# rev10.net
KiCad netlist of a schematic drawn in EAGLE
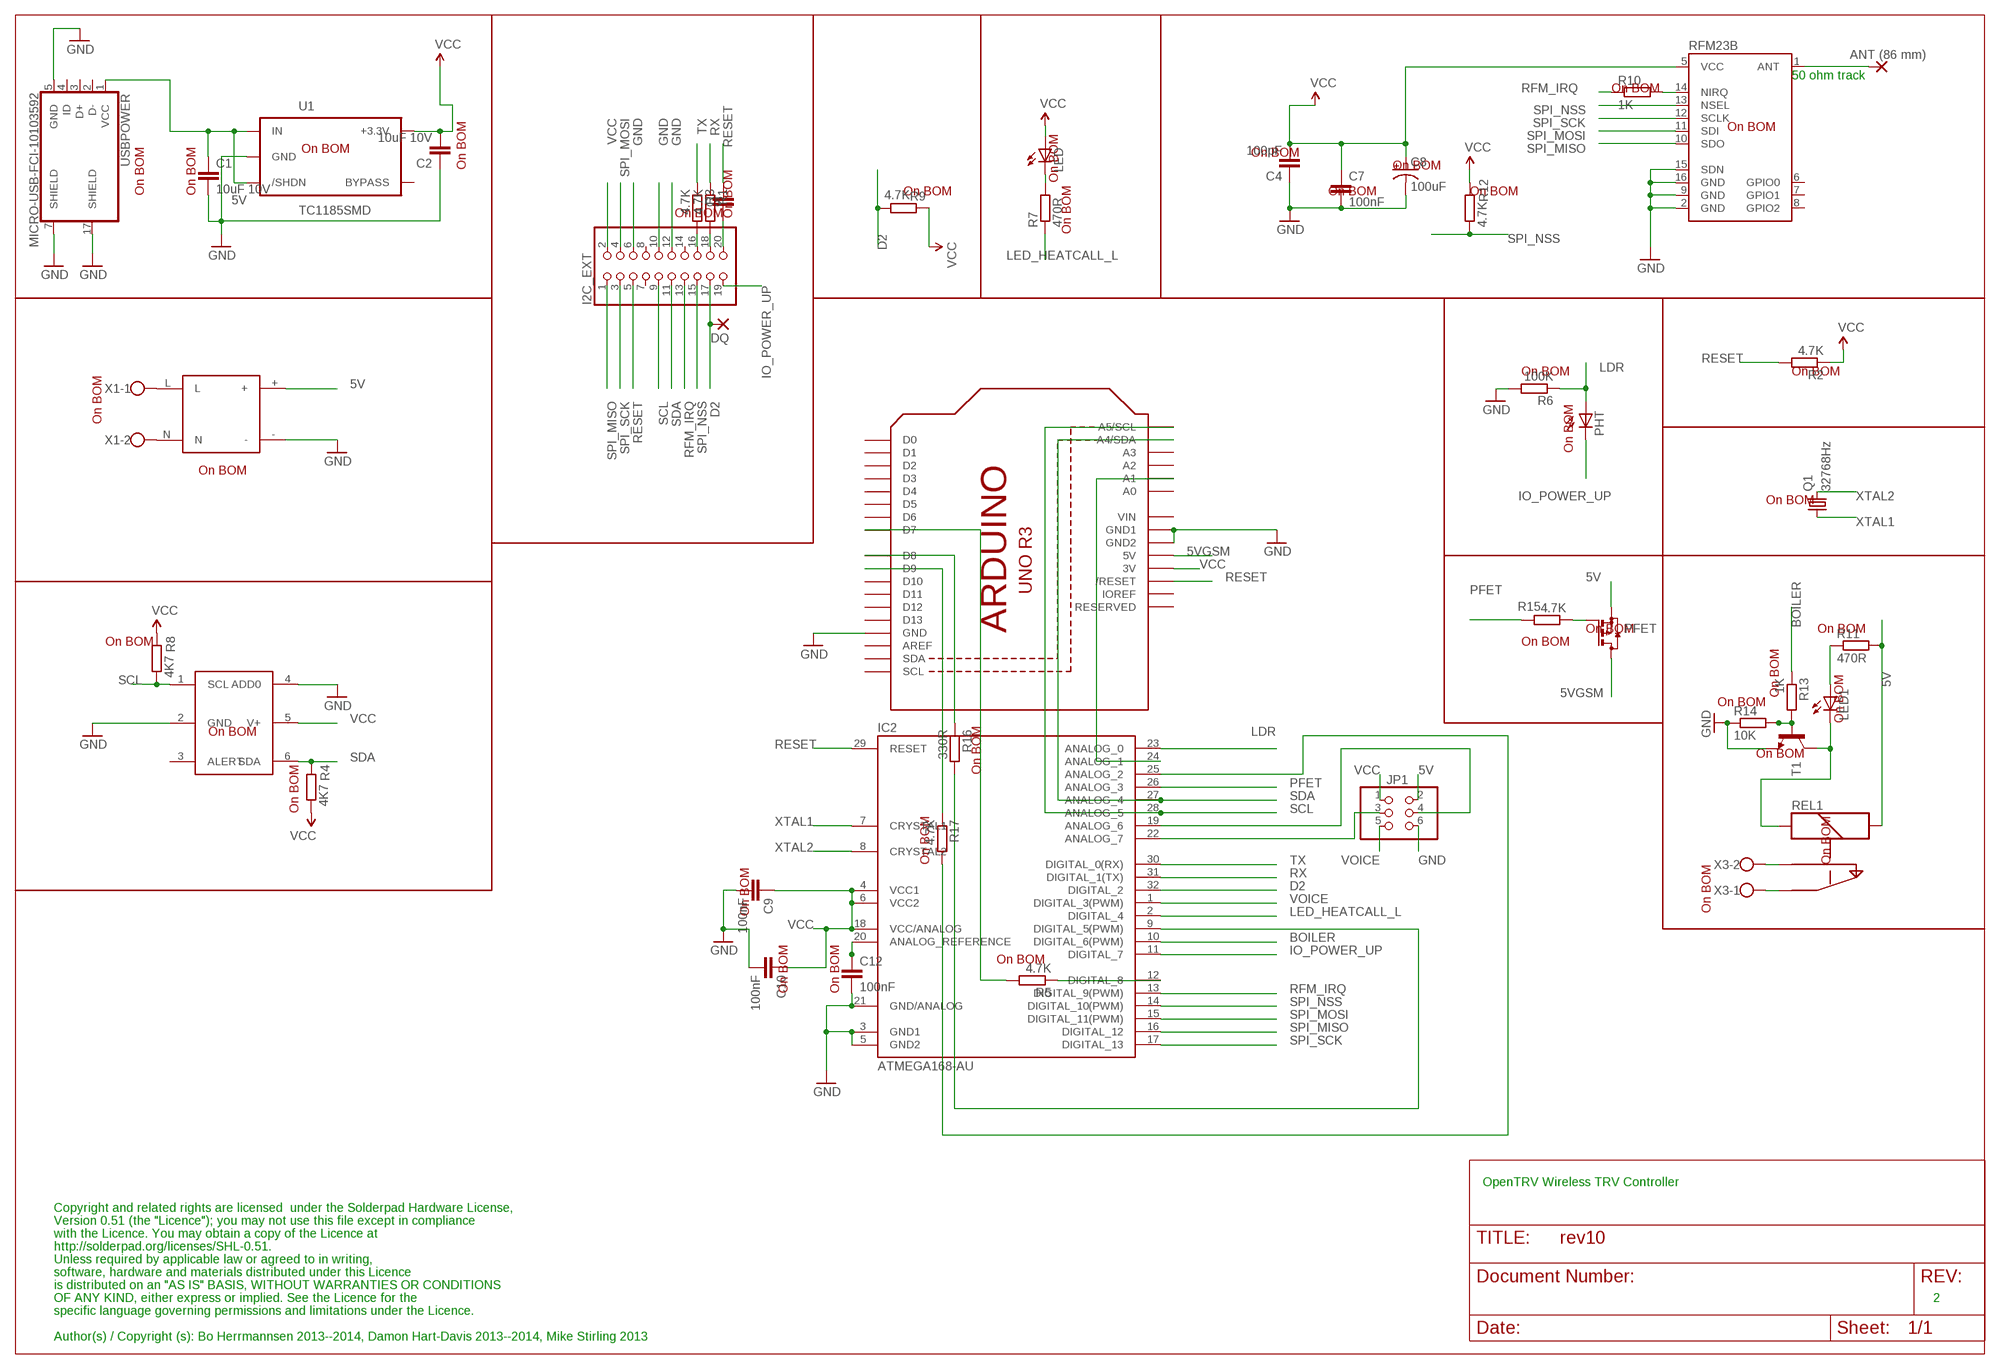
[diagram p0: schematic, sheet 1]

(export (version "E")
  (design (tool "Eeschema 10.0.6"))
  (components
    (comp (ref "ANT1")
      (value "ANT (86 mm)")
      (footprint "eagle-import:2,15_1,0")
      (libsource (lib "eagle-import") (part "2,15/1,0"))
    )
    (comp (ref "C1")
      (value "10uF 10V")
      (footprint "eagle-import:C0603")
      (libsource (lib "eagle-import") (part "C-EUC0603"))
    )
    (comp (ref "C2")
      (value "10uF 10V")
      (footprint "eagle-import:C0603")
      (libsource (lib "eagle-import") (part "C-EUC0603"))
    )
    (comp (ref "C4")
      (value "100pF")
      (footprint "eagle-import:C0603")
      (libsource (lib "eagle-import") (part "C-EUC0603"))
    )
    (comp (ref "C5")
      (value "100nF")
      (footprint "eagle-import:C0603")
      (libsource (lib "eagle-import") (part "C-EUC0603"))
    )
    (comp (ref "C7")
      (value "100nF")
      (footprint "eagle-import:C0603")
      (libsource (lib "eagle-import") (part "C-EUC0603"))
    )
    (comp (ref "C8")
      (value "100uF")
      (footprint "eagle-import:EIA3216")
      (libsource (lib "eagle-import") (part "CAP_POL1206"))
    )
    (comp (ref "C9")
      (value "100nF")
      (footprint "eagle-import:C0603")
      (libsource (lib "eagle-import") (part "C-EUC0603"))
    )
    (comp (ref "C10")
      (value "100nF")
      (footprint "eagle-import:C0603")
      (libsource (lib "eagle-import") (part "C-EUC0603"))
    )
    (comp (ref "C12")
      (value "100nF")
      (footprint "eagle-import:C0603")
      (libsource (lib "eagle-import") (part "C-EUC0603"))
    )
    (comp (ref "DQ")
      (value "2,15/1,0")
      (footprint "eagle-import:2,15_1,0")
      (libsource (lib "eagle-import") (part "2,15/1,0"))
    )
    (comp (ref "I2C_EXT")
      (value "PINHD-2X10")
      (footprint "eagle-import:2X10")
      (libsource (lib "eagle-import") (part "PINHD-2X10"))
    )
    (comp (ref "IC2")
      (value "ATMEGA168-AU")
      (footprint "eagle-import:TQFP32-08")
      (libsource (lib "eagle-import") (part "ATMEGA168-AU"))
    )
    (comp (ref "JP1")
      (value "PINHD-2X3")
      (footprint "eagle-import:2X03")
      (libsource (lib "eagle-import") (part "PINHD-2X3"))
    )
    (comp (ref "LED")
      (value "LEDCHIP-LED0603")
      (footprint "eagle-import:CHIP-LED0603")
      (libsource (lib "eagle-import") (part "LEDCHIP-LED0603"))
    )
    (comp (ref "LED1")
      (value "LEDCHIP-LED0603")
      (footprint "eagle-import:CHIP-LED0603")
      (libsource (lib "eagle-import") (part "LEDCHIP-LED0603"))
    )
    (comp (ref "PFET")
      (value "BSS84")
      (footprint "eagle-import:SOT23")
      (libsource (lib "eagle-import") (part "BSS84"))
    )
    (comp (ref "PHT")
      (value "BPX65")
      (footprint "eagle-import:BPX65")
      (fields (field (name "MPN") "BPX65."))
      (libsource (lib "eagle-import") (part "BPX65"))
    )
    (comp (ref "PSU")
      (value "VTX-214-010-205")
      (footprint "eagle-import:VTX-214-010-205")
      (libsource (lib "eagle-import") (part "VTX-214-010-205"))
    )
    (comp (ref "Q1")
      (value "32768Hz")
      (footprint "eagle-import:MC-306")
      (fields (field (name "MPN") "MC-306 60.0KHZ  100PPM ,12.5PF"))
      (libsource (lib "eagle-import") (part "MC-306"))
    )
    (comp (ref "R1")
      (value "4.7K")
      (footprint "eagle-import:R0603")
      (libsource (lib "eagle-import") (part "R-EU_R0603"))
    )
    (comp (ref "R2")
      (value "4.7K")
      (footprint "eagle-import:R0603")
      (libsource (lib "eagle-import") (part "R-EU_R0603"))
    )
    (comp (ref "R3")
      (value "4.7K")
      (footprint "eagle-import:R0603")
      (libsource (lib "eagle-import") (part "R-EU_R0603"))
    )
    (comp (ref "R4")
      (value "4K7")
      (footprint "eagle-import:R0603")
      (libsource (lib "eagle-import") (part "R-EU_R0603"))
    )
    (comp (ref "R5")
      (value "4.7K")
      (footprint "eagle-import:R0603")
      (libsource (lib "eagle-import") (part "R-EU_R0603"))
    )
    (comp (ref "R6")
      (value "100K")
      (footprint "eagle-import:R0603")
      (libsource (lib "eagle-import") (part "R-EU_R0603"))
    )
    (comp (ref "R7")
      (value "470R")
      (footprint "eagle-import:R0603")
      (libsource (lib "eagle-import") (part "R-EU_R0603"))
    )
    (comp (ref "R8")
      (value "4K7")
      (footprint "eagle-import:R0603")
      (libsource (lib "eagle-import") (part "R-EU_R0603"))
    )
    (comp (ref "R9")
      (value "4.7K")
      (footprint "eagle-import:R0603")
      (libsource (lib "eagle-import") (part "R-EU_R0603"))
    )
    (comp (ref "R10")
      (value "1K")
      (footprint "eagle-import:R0603")
      (libsource (lib "eagle-import") (part "R-EU_R0603"))
    )
    (comp (ref "R11")
      (value "470R")
      (footprint "eagle-import:R0603")
      (libsource (lib "eagle-import") (part "R-EU_R0603"))
    )
    (comp (ref "R12")
      (value "4.7K")
      (footprint "eagle-import:R0603")
      (libsource (lib "eagle-import") (part "R-EU_R0603"))
    )
    (comp (ref "R13")
      (value "1K")
      (footprint "eagle-import:R0603")
      (libsource (lib "eagle-import") (part "R-EU_R0603"))
    )
    (comp (ref "R14")
      (value "10K")
      (footprint "eagle-import:R0603")
      (libsource (lib "eagle-import") (part "R-EU_R0603"))
    )
    (comp (ref "R15")
      (value "4.7K")
      (footprint "eagle-import:R0603")
      (libsource (lib "eagle-import") (part "R-EU_R0603"))
    )
    (comp (ref "R16")
      (value "330R")
      (footprint "eagle-import:R0603")
      (libsource (lib "eagle-import") (part "R-EU_R0603"))
    )
    (comp (ref "R17")
      (value "4.7K")
      (footprint "eagle-import:R0603")
      (libsource (lib "eagle-import") (part "R-EU_R0603"))
    )
    (comp (ref "REL1")
      (value "OJE-SS-103HM")
      (footprint "eagle-import:OJE-SS-103HM")
      (libsource (lib "eagle-import") (part "OJE-SS-103HM"))
    )
    (comp (ref "RFM23B")
      (value "RFM23B")
      (footprint "eagle-import:RFM23-XXX-S1")
      (libsource (lib "eagle-import") (part "RFM23B"))
    )
    (comp (ref "T1")
      (value "MMBTH24LT1-NPN-SOT23-BEC")
      (footprint "eagle-import:SOT23-BEC")
      (libsource (lib "eagle-import") (part "-NPN-SOT23-BECMMBTH24LT1"))
    )
    (comp (ref "TMP112")
      (value "TMP1")
      (footprint "eagle-import:TMP112")
      (libsource (lib "eagle-import") (part "TMP112"))
    )
    (comp (ref "U$3")
      (value "ARDUINO")
      (footprint "eagle-import:ARDUINO")
      (libsource (lib "eagle-import") (part "ARDUINO"))
    )
    (comp (ref "U1")
      (value "TC1185SMD")
      (footprint "eagle-import:TC1185")
      (libsource (lib "eagle-import") (part "TC1185SMD"))
    )
    (comp (ref "USBPOWER")
      (value "MICRO-USB-FCI-10103592")
      (footprint "eagle-import:MICRO-USB-FCI-10103592")
      (libsource (lib "eagle-import") (part "MICRO-USB-FCI-10103592"))
    )
    (comp (ref "X1")
      (value "W237-102")
      (footprint "eagle-import:W237-102")
      (fields (field (name "MPN") "237-102"))
      (libsource (lib "eagle-import") (part "W237-102"))
    )
    (comp (ref "X3")
      (value "W237-102")
      (footprint "eagle-import:W237-102")
      (fields (field (name "MPN") "237-102"))
      (libsource (lib "eagle-import") (part "W237-102"))
    )
  )
  (nets
    (net (code "1") (name "/5V") (class "Default")
      (node (ref "C1") (pin "1") (pinfunction "1_1") (pintype "passive"))
      (node (ref "JP1") (pin "2") (pinfunction "2_2") (pintype "passive"))
      (node (ref "PFET") (pin "2") (pinfunction "S_2") (pintype "passive"))
      (node (ref "PSU") (pin "+") (pinfunction "+_+") (pintype "bidirectional"))
      (node (ref "R11") (pin "2") (pinfunction "2_2") (pintype "passive"))
      (node (ref "REL1") (pin "S2") (pinfunction "S2_S2") (pintype "passive"))
      (node (ref "U1") (pin "1") (pinfunction "IN_1") (pintype "passive"))
      (node (ref "U1") (pin "3") (pinfunction "/SHDN_3") (pintype "passive"))
      (node (ref "USBPOWER") (pin "1") (pinfunction "VCC_1") (pintype "bidirectional"))
    )
    (net (code "2") (name "/5VGSM") (class "Default")
      (node (ref "PFET") (pin "3") (pinfunction "D_3") (pintype "passive"))
      (node (ref "U$3") (pin "5V") (pinfunction "5V_5V") (pintype "power_in"))
    )
    (net (code "3") (name "/BOILER") (class "Default")
      (node (ref "IC2") (pin "10") (pinfunction "DIGITAL_6(PWM)_10") (pintype "bidirectional"))
      (node (ref "R13") (pin "1") (pinfunction "1_1") (pintype "passive"))
    )
    (net (code "4") (name "/D2") (class "Default")
      (node (ref "DQ") (pin "1") (pinfunction "P_1") (pintype "passive"))
      (node (ref "I2C_EXT") (pin "17") (pinfunction "17_17") (pintype "passive"))
      (node (ref "IC2") (pin "32") (pinfunction "DIGITAL_2_32") (pintype "bidirectional"))
      (node (ref "R9") (pin "1") (pinfunction "1_1") (pintype "passive"))
    )
    (net (code "5") (name "/IO_POWER_UP") (class "Default")
      (node (ref "I2C_EXT") (pin "19") (pinfunction "19_19") (pintype "passive"))
      (node (ref "IC2") (pin "11") (pinfunction "DIGITAL_7_11") (pintype "bidirectional"))
      (node (ref "PHT") (pin "K") (pinfunction "C_K") (pintype "passive"))
    )
    (net (code "6") (name "/LDR") (class "Default")
      (node (ref "IC2") (pin "23") (pinfunction "ANALOG_0_23") (pintype "bidirectional"))
      (node (ref "PHT") (pin "A") (pinfunction "A_A") (pintype "passive"))
      (node (ref "R6") (pin "1") (pinfunction "1_1") (pintype "passive"))
    )
    (net (code "7") (name "/LED_HEATCALL_L") (class "Default")
      (node (ref "IC2") (pin "2") (pinfunction "DIGITAL_4_2") (pintype "bidirectional"))
      (node (ref "R7") (pin "1") (pinfunction "1_1") (pintype "passive"))
    )
    (net (code "8") (name "/PFET") (class "Default")
      (node (ref "IC2") (pin "26") (pinfunction "ANALOG_3_26") (pintype "bidirectional"))
      (node (ref "R15") (pin "2") (pinfunction "2_2") (pintype "passive"))
    )
    (net (code "9") (name "/RESET") (class "Default")
      (node (ref "C5") (pin "1") (pinfunction "1_1") (pintype "passive"))
      (node (ref "I2C_EXT") (pin "5") (pinfunction "5_5") (pintype "passive"))
      (node (ref "IC2") (pin "29") (pinfunction "RESET_29") (pintype "bidirectional"))
      (node (ref "R2") (pin "2") (pinfunction "2_2") (pintype "passive"))
      (node (ref "U$3") (pin "RESET") (pinfunction "/RESET_RESET") (pintype "bidirectional"))
    )
    (net (code "10") (name "/RFM_IRQ") (class "Default")
      (node (ref "I2C_EXT") (pin "13") (pinfunction "13_13") (pintype "passive"))
      (node (ref "IC2") (pin "13") (pinfunction "DIGITAL_9(PWM)_13") (pintype "bidirectional"))
      (node (ref "R10") (pin "1") (pinfunction "1_1") (pintype "passive"))
    )
    (net (code "11") (name "/RX") (class "Default")
      (node (ref "IC2") (pin "31") (pinfunction "DIGITAL_1(TX)_31") (pintype "bidirectional"))
      (node (ref "R1") (pin "1") (pinfunction "1_1") (pintype "passive"))
    )
    (net (code "12") (name "/SCL") (class "Default")
      (node (ref "I2C_EXT") (pin "9") (pinfunction "9_9") (pintype "passive"))
      (node (ref "IC2") (pin "28") (pinfunction "ANALOG_5_28") (pintype "bidirectional"))
      (node (ref "R8") (pin "1") (pinfunction "1_1") (pintype "passive"))
      (node (ref "TMP112") (pin "1") (pinfunction "SCL_1") (pintype "bidirectional"))
      (node (ref "U$3") (pin "A5") (pinfunction "A5/SCL_A5") (pintype "bidirectional"))
    )
    (net (code "13") (name "/SDA") (class "Default")
      (node (ref "I2C_EXT") (pin "11") (pinfunction "11_11") (pintype "passive"))
      (node (ref "IC2") (pin "27") (pinfunction "ANALOG_4_27") (pintype "bidirectional"))
      (node (ref "R4") (pin "2") (pinfunction "2_2") (pintype "passive"))
      (node (ref "TMP112") (pin "6") (pinfunction "SDA_6") (pintype "bidirectional"))
      (node (ref "U$3") (pin "A4") (pinfunction "A4/SDA_A4") (pintype "bidirectional"))
    )
    (net (code "14") (name "/SPI_MISO") (class "Default")
      (node (ref "I2C_EXT") (pin "1") (pinfunction "1_1") (pintype "passive"))
      (node (ref "IC2") (pin "16") (pinfunction "DIGITAL_12_16") (pintype "bidirectional"))
      (node (ref "RFM23B") (pin "10") (pinfunction "SDO_10") (pintype "output"))
    )
    (net (code "15") (name "/SPI_MOSI") (class "Default")
      (node (ref "I2C_EXT") (pin "4") (pinfunction "4_4") (pintype "passive"))
      (node (ref "IC2") (pin "15") (pinfunction "DIGITAL_11(PWM)_15") (pintype "bidirectional"))
      (node (ref "RFM23B") (pin "11") (pinfunction "SDI_11") (pintype "input"))
    )
    (net (code "16") (name "/SPI_NSS") (class "Default")
      (node (ref "I2C_EXT") (pin "15") (pinfunction "15_15") (pintype "passive"))
      (node (ref "IC2") (pin "14") (pinfunction "DIGITAL_10(PWM)_14") (pintype "bidirectional"))
      (node (ref "R12") (pin "1") (pinfunction "1_1") (pintype "passive"))
      (node (ref "RFM23B") (pin "13") (pinfunction "NSEL_13") (pintype "input"))
    )
    (net (code "17") (name "/SPI_SCK") (class "Default")
      (node (ref "I2C_EXT") (pin "3") (pinfunction "3_3") (pintype "passive"))
      (node (ref "IC2") (pin "17") (pinfunction "DIGITAL_13_17") (pintype "bidirectional"))
      (node (ref "RFM23B") (pin "12") (pinfunction "SCLK_12") (pintype "input"))
    )
    (net (code "18") (name "/TX") (class "Default")
      (node (ref "IC2") (pin "30") (pinfunction "DIGITAL_0(RX)_30") (pintype "bidirectional"))
      (node (ref "R3") (pin "1") (pinfunction "1_1") (pintype "passive"))
    )
    (net (code "19") (name "/VIN") (class "Default")
      (node (ref "U$3") (pin "VIN") (pinfunction "VIN_VIN") (pintype "power_in"))
    )
    (net (code "20") (name "/VOICE") (class "Default")
      (node (ref "IC2") (pin "1") (pinfunction "DIGITAL_3(PWM)_1") (pintype "bidirectional"))
      (node (ref "JP1") (pin "5") (pinfunction "5_5") (pintype "passive"))
    )
    (net (code "21") (name "/XTAL1") (class "Default")
      (node (ref "IC2") (pin "7") (pinfunction "CRYSTAL1_7") (pintype "bidirectional"))
      (node (ref "Q1") (pin "1") (pinfunction "1_1") (pintype "passive"))
    )
    (net (code "22") (name "/XTAL2") (class "Default")
      (node (ref "IC2") (pin "8") (pinfunction "CRYSTAL2_8") (pintype "bidirectional"))
      (node (ref "Q1") (pin "4") (pinfunction "2_4") (pintype "passive"))
    )
    (net (code "23") (name "GND") (class "Default")
      (node (ref "C1") (pin "2") (pinfunction "2_2") (pintype "passive"))
      (node (ref "C10") (pin "2") (pinfunction "2_2") (pintype "passive"))
      (node (ref "C12") (pin "2") (pinfunction "2_2") (pintype "passive"))
      (node (ref "C2") (pin "1") (pinfunction "1_1") (pintype "passive"))
      (node (ref "C4") (pin "1") (pinfunction "1_1") (pintype "passive"))
      (node (ref "C7") (pin "2") (pinfunction "2_2") (pintype "passive"))
      (node (ref "C8") (pin "C") (pinfunction "-_C") (pintype "passive"))
      (node (ref "C9") (pin "2") (pinfunction "2_2") (pintype "passive"))
      (node (ref "I2C_EXT") (pin "10") (pinfunction "10_10") (pintype "passive"))
      (node (ref "I2C_EXT") (pin "12") (pinfunction "12_12") (pintype "passive"))
      (node (ref "I2C_EXT") (pin "6") (pinfunction "6_6") (pintype "passive"))
      (node (ref "IC2") (pin "21") (pinfunction "GND/ANALOG_21") (pintype "power_in"))
      (node (ref "IC2") (pin "3") (pinfunction "GND1_3") (pintype "power_in"))
      (node (ref "IC2") (pin "5") (pinfunction "GND2_5") (pintype "power_in"))
      (node (ref "JP1") (pin "6") (pinfunction "6_6") (pintype "passive"))
      (node (ref "PSU") (pin "-") (pinfunction "-_-") (pintype "bidirectional"))
      (node (ref "R14") (pin "1") (pinfunction "1_1") (pintype "passive"))
      (node (ref "R6") (pin "2") (pinfunction "2_2") (pintype "passive"))
      (node (ref "RFM23B") (pin "15") (pinfunction "SDN_15") (pintype "input"))
      (node (ref "RFM23B") (pin "16") (pinfunction "GND_16") (pintype "power_in"))
      (node (ref "RFM23B") (pin "2") (pinfunction "GND_2") (pintype "power_in"))
      (node (ref "RFM23B") (pin "9") (pinfunction "GND_9") (pintype "power_in"))
      (node (ref "T1") (pin "E") (pinfunction "E_E") (pintype "passive"))
      (node (ref "TMP112") (pin "2") (pinfunction "GND_2") (pintype "bidirectional"))
      (node (ref "TMP112") (pin "4") (pinfunction "ADD0_4") (pintype "bidirectional"))
      (node (ref "U$3") (pin "GND") (pinfunction "GND_GND") (pintype "power_in"))
      (node (ref "U$3") (pin "GND1") (pinfunction "GND1_GND1") (pintype "power_in"))
      (node (ref "U$3") (pin "GND2") (pinfunction "GND2_GND2") (pintype "power_in"))
      (node (ref "U1") (pin "2") (pinfunction "GND_2") (pintype "passive"))
      (node (ref "USBPOWER") (pin "17") (pinfunction "SHIELD_17") (pintype "bidirectional"))
      (node (ref "USBPOWER") (pin "5") (pinfunction "GND_5") (pintype "bidirectional"))
      (node (ref "USBPOWER") (pin "7") (pinfunction "SHIELD_7") (pintype "bidirectional"))
    )
    (net (code "24") (name "Net-(ANT1-P)") (class "Default")
      (node (ref "ANT1") (pin "1") (pinfunction "P_1") (pintype "passive"))
      (node (ref "RFM23B") (pin "1") (pinfunction "ANT_1") (pintype "bidirectional"))
    )
    (net (code "25") (name "Net-(C5-Pad2)") (class "Default")
      (node (ref "C5") (pin "2") (pinfunction "2_2") (pintype "passive"))
      (node (ref "I2C_EXT") (pin "20") (pinfunction "20_20") (pintype "passive"))
    )
    (net (code "26") (name "Net-(I2C_EXT-Pad16)") (class "Default")
      (node (ref "I2C_EXT") (pin "16") (pinfunction "16_16") (pintype "passive"))
      (node (ref "R3") (pin "2") (pinfunction "2_2") (pintype "passive"))
    )
    (net (code "27") (name "Net-(I2C_EXT-Pad18)") (class "Default")
      (node (ref "I2C_EXT") (pin "18") (pinfunction "18_18") (pintype "passive"))
      (node (ref "R1") (pin "2") (pinfunction "2_2") (pintype "passive"))
    )
    (net (code "28") (name "Net-(IC2-ANALOG_1)") (class "Default")
      (node (ref "IC2") (pin "24") (pinfunction "ANALOG_1_24") (pintype "bidirectional"))
      (node (ref "U$3") (pin "A1") (pinfunction "A1_A1") (pintype "bidirectional"))
    )
    (net (code "29") (name "Net-(IC2-ANALOG_2)") (class "Default")
      (node (ref "IC2") (pin "25") (pinfunction "ANALOG_2_25") (pintype "bidirectional"))
      (node (ref "R17") (pin "2") (pinfunction "2_2") (pintype "passive"))
    )
    (net (code "30") (name "Net-(IC2-ANALOG_6)") (class "Default")
      (node (ref "IC2") (pin "19") (pinfunction "ANALOG_6_19") (pintype "passive"))
      (node (ref "JP1") (pin "4") (pinfunction "4_4") (pintype "passive"))
    )
    (net (code "31") (name "Net-(IC2-ANALOG_7)") (class "Default")
      (node (ref "IC2") (pin "22") (pinfunction "ANALOG_7_22") (pintype "passive"))
      (node (ref "JP1") (pin "3") (pinfunction "3_3") (pintype "passive"))
    )
    (net (code "32") (name "Net-(IC2-ANALOG_REFERENCE)") (class "Default")
      (node (ref "C12") (pin "1") (pinfunction "1_1") (pintype "passive"))
      (node (ref "IC2") (pin "20") (pinfunction "ANALOG_REFERENCE_20") (pintype "passive"))
    )
    (net (code "33") (name "Net-(IC2-DIGITAL_5(PWM))") (class "Default")
      (node (ref "IC2") (pin "9") (pinfunction "DIGITAL_5(PWM)_9") (pintype "bidirectional"))
      (node (ref "R16") (pin "2") (pinfunction "2_2") (pintype "passive"))
    )
    (net (code "34") (name "Net-(IC2-DIGITAL_8)") (class "Default")
      (node (ref "IC2") (pin "12") (pinfunction "DIGITAL_8_12") (pintype "bidirectional"))
      (node (ref "R5") (pin "1") (pinfunction "1_1") (pintype "passive"))
    )
    (net (code "35") (name "Net-(LED-PadC)") (class "Default")
      (node (ref "LED") (pin "C") (pinfunction "C_C") (pintype "passive"))
      (node (ref "R7") (pin "2") (pinfunction "2_2") (pintype "passive"))
    )
    (net (code "36") (name "Net-(LED1-PadA)") (class "Default")
      (node (ref "LED1") (pin "A") (pinfunction "A_A") (pintype "passive"))
      (node (ref "R11") (pin "1") (pinfunction "1_1") (pintype "passive"))
    )
    (net (code "37") (name "Net-(LED1-PadC)") (class "Default")
      (node (ref "LED1") (pin "C") (pinfunction "C_C") (pintype "passive"))
      (node (ref "REL1") (pin "S1") (pinfunction "S1_S1") (pintype "passive"))
      (node (ref "T1") (pin "C") (pinfunction "C_C") (pintype "passive"))
    )
    (net (code "38") (name "Net-(PFET-G)") (class "Default")
      (node (ref "PFET") (pin "1") (pinfunction "G_1") (pintype "passive"))
      (node (ref "R15") (pin "1") (pinfunction "1_1") (pintype "passive"))
    )
    (net (code "39") (name "Net-(R5-Pad2)") (class "Default")
      (node (ref "R5") (pin "2") (pinfunction "2_2") (pintype "passive"))
      (node (ref "U$3") (pin "D7") (pinfunction "D7_D7") (pintype "bidirectional"))
    )
    (net (code "40") (name "Net-(R13-Pad2)") (class "Default")
      (node (ref "R13") (pin "2") (pinfunction "2_2") (pintype "passive"))
      (node (ref "R14") (pin "2") (pinfunction "2_2") (pintype "passive"))
      (node (ref "T1") (pin "B") (pinfunction "B_B") (pintype "passive"))
    )
    (net (code "41") (name "Net-(R16-Pad1)") (class "Default")
      (node (ref "R16") (pin "1") (pinfunction "1_1") (pintype "passive"))
      (node (ref "U$3") (pin "D8") (pinfunction "D8_D8") (pintype "bidirectional"))
    )
    (net (code "42") (name "Net-(R17-Pad1)") (class "Default")
      (node (ref "R17") (pin "1") (pinfunction "1_1") (pintype "passive"))
      (node (ref "U$3") (pin "D9") (pinfunction "D9_D9") (pintype "bidirectional"))
    )
    (net (code "43") (name "Net-(RFM23B-NIRQ)") (class "Default")
      (node (ref "R10") (pin "2") (pinfunction "2_2") (pintype "passive"))
      (node (ref "RFM23B") (pin "14") (pinfunction "NIRQ_14") (pintype "output"))
    )
    (net (code "44") (name "Net-(X1A-KL)") (class "Default")
      (node (ref "PSU") (pin "L") (pinfunction "L_L") (pintype "bidirectional"))
      (node (ref "X1") (pin "1") (pinfunction "KL_1") (pintype "passive"))
    )
    (net (code "45") (name "Net-(X1B-KL)") (class "Default")
      (node (ref "PSU") (pin "N") (pinfunction "N_N") (pintype "bidirectional"))
      (node (ref "X1") (pin "2") (pinfunction "KL_2") (pintype "passive"))
    )
    (net (code "46") (name "Net-(X3A-KL)") (class "Default")
      (node (ref "REL1") (pin "C") (pinfunction "C_C") (pintype "passive"))
      (node (ref "X3") (pin "1") (pinfunction "KL_1") (pintype "passive"))
    )
    (net (code "47") (name "Net-(X3B-KL)") (class "Default")
      (node (ref "REL1") (pin "S") (pinfunction "S_S") (pintype "passive"))
      (node (ref "X3") (pin "2") (pinfunction "KL_2") (pintype "passive"))
    )
    (net (code "48") (name "VCC") (class "Default")
      (node (ref "C10") (pin "1") (pinfunction "1_1") (pintype "passive"))
      (node (ref "C2") (pin "2") (pinfunction "2_2") (pintype "passive"))
      (node (ref "C4") (pin "2") (pinfunction "2_2") (pintype "passive"))
      (node (ref "C7") (pin "1") (pinfunction "1_1") (pintype "passive"))
      (node (ref "C8") (pin "A") (pinfunction "+_A") (pintype "passive"))
      (node (ref "C9") (pin "1") (pinfunction "1_1") (pintype "passive"))
      (node (ref "I2C_EXT") (pin "2") (pinfunction "2_2") (pintype "passive"))
      (node (ref "IC2") (pin "18") (pinfunction "VCC/ANALOG_18") (pintype "passive"))
      (node (ref "IC2") (pin "4") (pinfunction "VCC1_4") (pintype "power_in"))
      (node (ref "IC2") (pin "6") (pinfunction "VCC2_6") (pintype "power_in"))
      (node (ref "JP1") (pin "1") (pinfunction "1_1") (pintype "passive"))
      (node (ref "LED") (pin "A") (pinfunction "A_A") (pintype "passive"))
      (node (ref "R12") (pin "2") (pinfunction "2_2") (pintype "passive"))
      (node (ref "R2") (pin "1") (pinfunction "1_1") (pintype "passive"))
      (node (ref "R4") (pin "1") (pinfunction "1_1") (pintype "passive"))
      (node (ref "R8") (pin "2") (pinfunction "2_2") (pintype "passive"))
      (node (ref "R9") (pin "2") (pinfunction "2_2") (pintype "passive"))
      (node (ref "RFM23B") (pin "5") (pinfunction "VCC_5") (pintype "bidirectional"))
      (node (ref "TMP112") (pin "5") (pinfunction "V+_5") (pintype "bidirectional"))
      (node (ref "U$3") (pin "3V") (pinfunction "3V_3V") (pintype "power_in"))
      (node (ref "U1") (pin "5") (pinfunction "+3.3V_5") (pintype "power_in"))
    )
    (net (code "49") (name "unconnected-(I2C_EXT-Pad7)") (class "Default")
      (node (ref "I2C_EXT") (pin "7") (pinfunction "7_7") (pintype "passive"))
    )
    (net (code "50") (name "unconnected-(I2C_EXT-Pad8)") (class "Default")
      (node (ref "I2C_EXT") (pin "8") (pinfunction "8_8") (pintype "passive"))
    )
    (net (code "51") (name "unconnected-(I2C_EXT-Pad14)") (class "Default")
      (node (ref "I2C_EXT") (pin "14") (pinfunction "14_14") (pintype "passive"))
    )
    (net (code "52") (name "unconnected-(RFM23B-GPIO0-Pad6)") (class "Default")
      (node (ref "RFM23B") (pin "6") (pinfunction "GPIO0_6") (pintype "bidirectional"))
    )
    (net (code "53") (name "unconnected-(RFM23B-GPIO1-Pad7)") (class "Default")
      (node (ref "RFM23B") (pin "7") (pinfunction "GPIO1_7") (pintype "bidirectional"))
    )
    (net (code "54") (name "unconnected-(RFM23B-GPIO2-Pad8)") (class "Default")
      (node (ref "RFM23B") (pin "8") (pinfunction "GPIO2_8") (pintype "bidirectional"))
    )
    (net (code "55") (name "unconnected-(TMP112-ALERT-Pad3)") (class "Default")
      (node (ref "TMP112") (pin "3") (pinfunction "ALERT_3") (pintype "bidirectional"))
    )
    (net (code "56") (name "unconnected-(U$3-PadA0)") (class "Default")
      (node (ref "U$3") (pin "A0") (pinfunction "A0_A0") (pintype "bidirectional"))
    )
    (net (code "57") (name "unconnected-(U$3-PadA2)") (class "Default")
      (node (ref "U$3") (pin "A2") (pinfunction "A2_A2") (pintype "bidirectional"))
    )
    (net (code "58") (name "unconnected-(U$3-PadA3)") (class "Default")
      (node (ref "U$3") (pin "A3") (pinfunction "A3_A3") (pintype "bidirectional"))
    )
    (net (code "59") (name "unconnected-(U$3-PadAREF)") (class "Default")
      (node (ref "U$3") (pin "AREF") (pinfunction "AREF_AREF") (pintype "bidirectional"))
    )
    (net (code "60") (name "unconnected-(U$3-PadD0)") (class "Default")
      (node (ref "U$3") (pin "D0") (pinfunction "D0_D0") (pintype "bidirectional"))
    )
    (net (code "61") (name "unconnected-(U$3-PadD1)") (class "Default")
      (node (ref "U$3") (pin "D1") (pinfunction "D1_D1") (pintype "bidirectional"))
    )
    (net (code "62") (name "unconnected-(U$3-PadD2)") (class "Default")
      (node (ref "U$3") (pin "D2") (pinfunction "D2_D2") (pintype "bidirectional"))
    )
    (net (code "63") (name "unconnected-(U$3-PadD3)") (class "Default")
      (node (ref "U$3") (pin "D3") (pinfunction "D3_D3") (pintype "bidirectional"))
    )
    (net (code "64") (name "unconnected-(U$3-PadD4)") (class "Default")
      (node (ref "U$3") (pin "D4") (pinfunction "D4_D4") (pintype "bidirectional"))
    )
    (net (code "65") (name "unconnected-(U$3-PadD5)") (class "Default")
      (node (ref "U$3") (pin "D5") (pinfunction "D5_D5") (pintype "bidirectional"))
    )
    (net (code "66") (name "unconnected-(U$3-PadD6)") (class "Default")
      (node (ref "U$3") (pin "D6") (pinfunction "D6_D6") (pintype "bidirectional"))
    )
    (net (code "67") (name "unconnected-(U$3-PadD10)") (class "Default")
      (node (ref "U$3") (pin "D10") (pinfunction "D10_D10") (pintype "bidirectional"))
    )
    (net (code "68") (name "unconnected-(U$3-PadD11)") (class "Default")
      (node (ref "U$3") (pin "D11") (pinfunction "D11_D11") (pintype "bidirectional"))
    )
    (net (code "69") (name "unconnected-(U$3-PadD12)") (class "Default")
      (node (ref "U$3") (pin "D12") (pinfunction "D12_D12") (pintype "bidirectional"))
    )
    (net (code "70") (name "unconnected-(U$3-PadD13)") (class "Default")
      (node (ref "U$3") (pin "D13") (pinfunction "D13_D13") (pintype "bidirectional"))
    )
    (net (code "71") (name "unconnected-(U$3-PadIOREF)") (class "Default")
      (node (ref "U$3") (pin "IOREF") (pinfunction "IOREF_IOREF") (pintype "output"))
    )
    (net (code "72") (name "unconnected-(U$3-PadRESERVED)") (class "Default")
      (node (ref "U$3") (pin "RESERVED") (pinfunction "RESERVED_RESERVED") (pintype "no_connect"))
    )
    (net (code "73") (name "unconnected-(U$3-PadSCL)") (class "Default")
      (node (ref "U$3") (pin "SCL") (pinfunction "SCL_SCL") (pintype "bidirectional"))
    )
    (net (code "74") (name "unconnected-(U$3-PadSDA)") (class "Default")
      (node (ref "U$3") (pin "SDA") (pinfunction "SDA_SDA") (pintype "bidirectional"))
    )
    (net (code "75") (name "unconnected-(U1-BYPASS-Pad4)") (class "Default")
      (node (ref "U1") (pin "4") (pinfunction "BYPASS_4") (pintype "passive"))
    )
    (net (code "76") (name "unconnected-(USBPOWER-D+-Pad3)") (class "Default")
      (node (ref "USBPOWER") (pin "3") (pinfunction "D+_3") (pintype "bidirectional"))
    )
    (net (code "77") (name "unconnected-(USBPOWER-D--Pad2)") (class "Default")
      (node (ref "USBPOWER") (pin "2") (pinfunction "D-_2") (pintype "bidirectional"))
    )
    (net (code "78") (name "unconnected-(USBPOWER-ID-Pad4)") (class "Default")
      (node (ref "USBPOWER") (pin "4") (pinfunction "ID_4") (pintype "bidirectional"))
    )
  )
)
